# DR_EIB-128_Circle.net
KiCad netlist of a schematic drawn in EAGLE
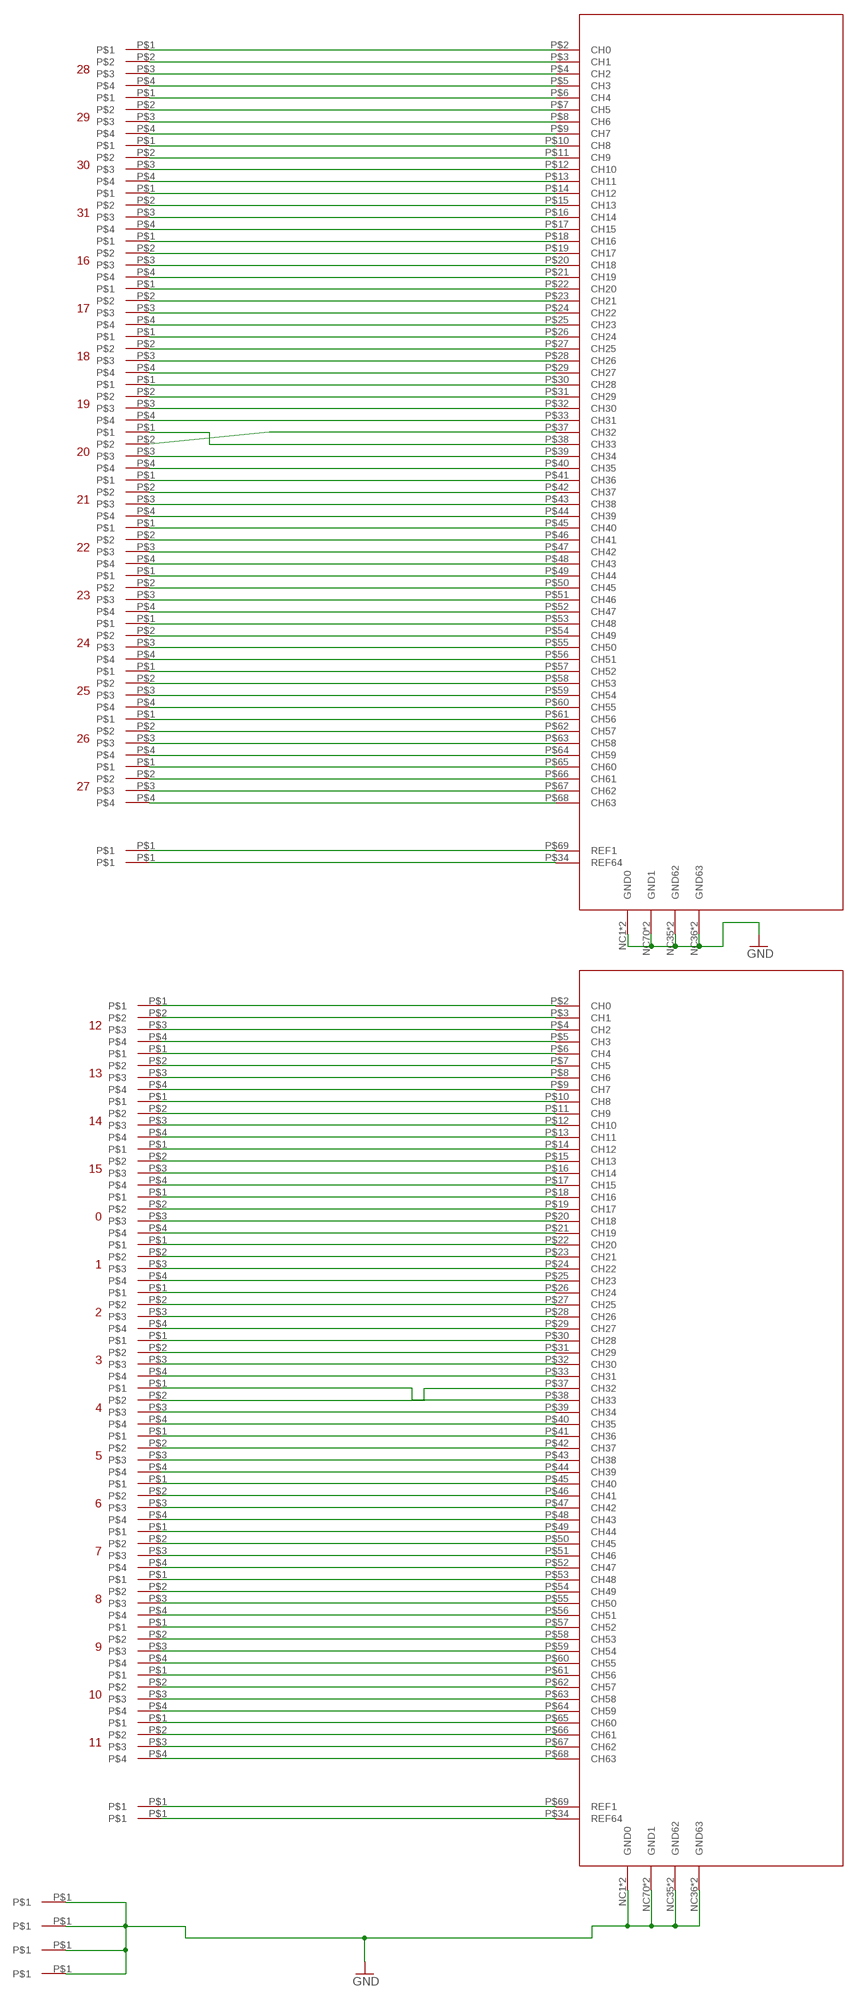
[diagram p0: schematic, sheet 1]

(export (version "E")
  (design (tool "Eeschema 10.0.6"))
  (components
    (comp (ref "0")
      (value "TETRODE_1.5IN_RADIUS")
      (footprint "eagle-import:TETRODE_1.5IN_RADIUS")
      (libsource (lib "eagle-import") (part "TETRODE_1.5IN_RADIUS"))
    )
    (comp (ref "1")
      (value "TETRODE_1.5IN_RADIUS")
      (footprint "eagle-import:TETRODE_1.5IN_RADIUS")
      (libsource (lib "eagle-import") (part "TETRODE_1.5IN_RADIUS"))
    )
    (comp (ref "2")
      (value "TETRODE_1.5IN_RADIUS")
      (footprint "eagle-import:TETRODE_1.5IN_RADIUS")
      (libsource (lib "eagle-import") (part "TETRODE_1.5IN_RADIUS"))
    )
    (comp (ref "3")
      (value "TETRODE_1.5IN_RADIUS")
      (footprint "eagle-import:TETRODE_1.5IN_RADIUS")
      (libsource (lib "eagle-import") (part "TETRODE_1.5IN_RADIUS"))
    )
    (comp (ref "4")
      (value "TETRODE_1.5IN_RADIUS")
      (footprint "eagle-import:TETRODE_1.5IN_RADIUS")
      (libsource (lib "eagle-import") (part "TETRODE_1.5IN_RADIUS"))
    )
    (comp (ref "5")
      (value "TETRODE_1.5IN_RADIUS")
      (footprint "eagle-import:TETRODE_1.5IN_RADIUS")
      (libsource (lib "eagle-import") (part "TETRODE_1.5IN_RADIUS"))
    )
    (comp (ref "6")
      (value "TETRODE_1.5IN_RADIUS")
      (footprint "eagle-import:TETRODE_1.5IN_RADIUS")
      (libsource (lib "eagle-import") (part "TETRODE_1.5IN_RADIUS"))
    )
    (comp (ref "7")
      (value "TETRODE_1.5IN_RADIUS")
      (footprint "eagle-import:TETRODE_1.5IN_RADIUS")
      (libsource (lib "eagle-import") (part "TETRODE_1.5IN_RADIUS"))
    )
    (comp (ref "8")
      (value "TETRODE_1.5IN_RADIUS")
      (footprint "eagle-import:TETRODE_1.5IN_RADIUS")
      (libsource (lib "eagle-import") (part "TETRODE_1.5IN_RADIUS"))
    )
    (comp (ref "9")
      (value "TETRODE_1.5IN_RADIUS")
      (footprint "eagle-import:TETRODE_1.5IN_RADIUS")
      (libsource (lib "eagle-import") (part "TETRODE_1.5IN_RADIUS"))
    )
    (comp (ref "10")
      (value "TETRODE_1.5IN_RADIUS")
      (footprint "eagle-import:TETRODE_1.5IN_RADIUS")
      (libsource (lib "eagle-import") (part "TETRODE_1.5IN_RADIUS"))
    )
    (comp (ref "11")
      (value "TETRODE_1.5IN_RADIUS")
      (footprint "eagle-import:TETRODE_1.5IN_RADIUS")
      (libsource (lib "eagle-import") (part "TETRODE_1.5IN_RADIUS"))
    )
    (comp (ref "12")
      (value "TETRODE_1.5IN_RADIUS")
      (footprint "eagle-import:TETRODE_1.5IN_RADIUS")
      (libsource (lib "eagle-import") (part "TETRODE_1.5IN_RADIUS"))
    )
    (comp (ref "13")
      (value "TETRODE_1.5IN_RADIUS")
      (footprint "eagle-import:TETRODE_1.5IN_RADIUS")
      (libsource (lib "eagle-import") (part "TETRODE_1.5IN_RADIUS"))
    )
    (comp (ref "14")
      (value "TETRODE_1.5IN_RADIUS")
      (footprint "eagle-import:TETRODE_1.5IN_RADIUS")
      (libsource (lib "eagle-import") (part "TETRODE_1.5IN_RADIUS"))
    )
    (comp (ref "15")
      (value "TETRODE_1.5IN_RADIUS")
      (footprint "eagle-import:TETRODE_1.5IN_RADIUS")
      (libsource (lib "eagle-import") (part "TETRODE_1.5IN_RADIUS"))
    )
    (comp (ref "16")
      (value "TETRODE_1.5IN_RADIUS")
      (footprint "eagle-import:TETRODE_1.5IN_RADIUS")
      (libsource (lib "eagle-import") (part "TETRODE_1.5IN_RADIUS"))
    )
    (comp (ref "17")
      (value "TETRODE_1.5IN_RADIUS")
      (footprint "eagle-import:TETRODE_1.5IN_RADIUS")
      (libsource (lib "eagle-import") (part "TETRODE_1.5IN_RADIUS"))
    )
    (comp (ref "18")
      (value "TETRODE_1.5IN_RADIUS")
      (footprint "eagle-import:TETRODE_1.5IN_RADIUS")
      (libsource (lib "eagle-import") (part "TETRODE_1.5IN_RADIUS"))
    )
    (comp (ref "19")
      (value "TETRODE_1.5IN_RADIUS")
      (footprint "eagle-import:TETRODE_1.5IN_RADIUS")
      (libsource (lib "eagle-import") (part "TETRODE_1.5IN_RADIUS"))
    )
    (comp (ref "20")
      (value "TETRODE_1.5IN_RADIUS")
      (footprint "eagle-import:TETRODE_1.5IN_RADIUS")
      (libsource (lib "eagle-import") (part "TETRODE_1.5IN_RADIUS"))
    )
    (comp (ref "21")
      (value "TETRODE_1.5IN_RADIUS")
      (footprint "eagle-import:TETRODE_1.5IN_RADIUS")
      (libsource (lib "eagle-import") (part "TETRODE_1.5IN_RADIUS"))
    )
    (comp (ref "22")
      (value "TETRODE_1.5IN_RADIUS")
      (footprint "eagle-import:TETRODE_1.5IN_RADIUS")
      (libsource (lib "eagle-import") (part "TETRODE_1.5IN_RADIUS"))
    )
    (comp (ref "23")
      (value "TETRODE_1.5IN_RADIUS")
      (footprint "eagle-import:TETRODE_1.5IN_RADIUS")
      (libsource (lib "eagle-import") (part "TETRODE_1.5IN_RADIUS"))
    )
    (comp (ref "24")
      (value "TETRODE_1.5IN_RADIUS")
      (footprint "eagle-import:TETRODE_1.5IN_RADIUS")
      (libsource (lib "eagle-import") (part "TETRODE_1.5IN_RADIUS"))
    )
    (comp (ref "25")
      (value "TETRODE_1.5IN_RADIUS")
      (footprint "eagle-import:TETRODE_1.5IN_RADIUS")
      (libsource (lib "eagle-import") (part "TETRODE_1.5IN_RADIUS"))
    )
    (comp (ref "26")
      (value "TETRODE_1.5IN_RADIUS")
      (footprint "eagle-import:TETRODE_1.5IN_RADIUS")
      (libsource (lib "eagle-import") (part "TETRODE_1.5IN_RADIUS"))
    )
    (comp (ref "27")
      (value "TETRODE_1.5IN_RADIUS")
      (footprint "eagle-import:TETRODE_1.5IN_RADIUS")
      (libsource (lib "eagle-import") (part "TETRODE_1.5IN_RADIUS"))
    )
    (comp (ref "28")
      (value "TETRODE_1.5IN_RADIUS")
      (footprint "eagle-import:TETRODE_1.5IN_RADIUS")
      (libsource (lib "eagle-import") (part "TETRODE_1.5IN_RADIUS"))
    )
    (comp (ref "29")
      (value "TETRODE_1.5IN_RADIUS")
      (footprint "eagle-import:TETRODE_1.5IN_RADIUS")
      (libsource (lib "eagle-import") (part "TETRODE_1.5IN_RADIUS"))
    )
    (comp (ref "30")
      (value "TETRODE_1.5IN_RADIUS")
      (footprint "eagle-import:TETRODE_1.5IN_RADIUS")
      (libsource (lib "eagle-import") (part "TETRODE_1.5IN_RADIUS"))
    )
    (comp (ref "31")
      (value "TETRODE_1.5IN_RADIUS")
      (footprint "eagle-import:TETRODE_1.5IN_RADIUS")
      (libsource (lib "eagle-import") (part "TETRODE_1.5IN_RADIUS"))
    )
    (comp (ref "U$1")
      (value "TARRAYSHUTTLEHOLE")
      (footprint "eagle-import:TARRAYSHUTTLEHOLE")
      (libsource (lib "eagle-import") (part "TARRAYSHUTTLEHOLE"))
    )
    (comp (ref "U$2")
      (value "TARRAYSHUTTLEHOLE")
      (footprint "eagle-import:TARRAYSHUTTLEHOLE")
      (libsource (lib "eagle-import") (part "TARRAYSHUTTLEHOLE"))
    )
    (comp (ref "U$4")
      (value "TARRAYSHUTTLEHOLE")
      (footprint "eagle-import:TARRAYSHUTTLEHOLE")
      (libsource (lib "eagle-import") (part "TARRAYSHUTTLEHOLE"))
    )
    (comp (ref "U$5")
      (value "TARRAYSHUTTLEHOLE")
      (footprint "eagle-import:TARRAYSHUTTLEHOLE")
      (libsource (lib "eagle-import") (part "TARRAYSHUTTLEHOLE"))
    )
    (comp (ref "U$6")
      (value "TARRAYSHUTTLEHOLE")
      (footprint "eagle-import:TARRAYSHUTTLEHOLE")
      (libsource (lib "eagle-import") (part "TARRAYSHUTTLEHOLE"))
    )
    (comp (ref "U$7")
      (value "TARRAYSHUTTLEHOLE")
      (footprint "eagle-import:TARRAYSHUTTLEHOLE")
      (libsource (lib "eagle-import") (part "TARRAYSHUTTLEHOLE"))
    )
    (comp (ref "U$8")
      (value "TARRAYSHUTTLEHOLE")
      (footprint "eagle-import:TARRAYSHUTTLEHOLE")
      (libsource (lib "eagle-import") (part "TARRAYSHUTTLEHOLE"))
    )
    (comp (ref "U$9")
      (value "TARRAYSHUTTLEHOLE")
      (footprint "eagle-import:TARRAYSHUTTLEHOLE")
      (libsource (lib "eagle-import") (part "TARRAYSHUTTLEHOLE"))
    )
    (comp (ref "U$10")
      (value "HIROSE-70PIN-HEADER-SEQUENTIAL")
      (footprint "eagle-import:DF40C-70DP-0.4V")
      (libsource (lib "eagle-import") (part "HIROSE-70PIN-HEADER-SEQUENTIAL"))
    )
    (comp (ref "U$11")
      (value "HIROSE-70PIN-HEADER-SEQUENTIAL")
      (footprint "eagle-import:DF40C-70DP-0.4V")
      (libsource (lib "eagle-import") (part "HIROSE-70PIN-HEADER-SEQUENTIAL"))
    )
  )
  (nets
    (net (code "1") (name "GND") (class "Default")
      (node (ref "U$1") (pin "P$1") (pinfunction "P$1_P$1") (pintype "bidirectional"))
      (node (ref "U$10") (pin "NC1") (pinfunction "GND0_NC1") (pintype "power_in"))
      (node (ref "U$10") (pin "NC35") (pinfunction "GND62_NC35") (pintype "power_in"))
      (node (ref "U$10") (pin "NC36") (pinfunction "GND63_NC36") (pintype "power_in"))
      (node (ref "U$10") (pin "NC70") (pinfunction "GND1_NC70") (pintype "power_in"))
      (node (ref "U$10") (pin "P$1") (pinfunction "GND0_P$1") (pintype "power_in"))
      (node (ref "U$10") (pin "P$35") (pinfunction "GND62_P$35") (pintype "power_in"))
      (node (ref "U$10") (pin "P$36") (pinfunction "GND63_P$36") (pintype "power_in"))
      (node (ref "U$10") (pin "P$70") (pinfunction "GND1_P$70") (pintype "power_in"))
      (node (ref "U$11") (pin "NC1") (pinfunction "GND0_NC1") (pintype "power_in"))
      (node (ref "U$11") (pin "NC35") (pinfunction "GND62_NC35") (pintype "power_in"))
      (node (ref "U$11") (pin "NC36") (pinfunction "GND63_NC36") (pintype "power_in"))
      (node (ref "U$11") (pin "NC70") (pinfunction "GND1_NC70") (pintype "power_in"))
      (node (ref "U$11") (pin "P$1") (pinfunction "GND0_P$1") (pintype "power_in"))
      (node (ref "U$11") (pin "P$35") (pinfunction "GND62_P$35") (pintype "power_in"))
      (node (ref "U$11") (pin "P$36") (pinfunction "GND63_P$36") (pintype "power_in"))
      (node (ref "U$11") (pin "P$70") (pinfunction "GND1_P$70") (pintype "power_in"))
      (node (ref "U$2") (pin "P$1") (pinfunction "P$1_P$1") (pintype "bidirectional"))
      (node (ref "U$4") (pin "P$1") (pinfunction "P$1_P$1") (pintype "bidirectional"))
      (node (ref "U$5") (pin "P$1") (pinfunction "P$1_P$1") (pintype "bidirectional"))
    )
    (net (code "2") (name "Net-(U$10-CH0)") (class "Default")
      (node (ref "28") (pin "P$1") (pinfunction "P$1_P$1") (pintype "bidirectional"))
      (node (ref "U$10") (pin "P$2") (pinfunction "CH0_P$2") (pintype "input"))
    )
    (net (code "3") (name "Net-(U$10-CH1)") (class "Default")
      (node (ref "28") (pin "P$2") (pinfunction "P$2_P$2") (pintype "bidirectional"))
      (node (ref "U$10") (pin "P$3") (pinfunction "CH1_P$3") (pintype "input"))
    )
    (net (code "4") (name "Net-(U$10-CH2)") (class "Default")
      (node (ref "28") (pin "P$3") (pinfunction "P$3_P$3") (pintype "bidirectional"))
      (node (ref "U$10") (pin "P$4") (pinfunction "CH2_P$4") (pintype "input"))
    )
    (net (code "5") (name "Net-(U$10-CH3)") (class "Default")
      (node (ref "28") (pin "P$4") (pinfunction "P$4_P$4") (pintype "bidirectional"))
      (node (ref "U$10") (pin "P$5") (pinfunction "CH3_P$5") (pintype "input"))
    )
    (net (code "6") (name "Net-(U$10-CH4)") (class "Default")
      (node (ref "29") (pin "P$1") (pinfunction "P$1_P$1") (pintype "bidirectional"))
      (node (ref "U$10") (pin "P$6") (pinfunction "CH4_P$6") (pintype "input"))
    )
    (net (code "7") (name "Net-(U$10-CH5)") (class "Default")
      (node (ref "29") (pin "P$2") (pinfunction "P$2_P$2") (pintype "bidirectional"))
      (node (ref "U$10") (pin "P$7") (pinfunction "CH5_P$7") (pintype "input"))
    )
    (net (code "8") (name "Net-(U$10-CH6)") (class "Default")
      (node (ref "29") (pin "P$3") (pinfunction "P$3_P$3") (pintype "bidirectional"))
      (node (ref "U$10") (pin "P$8") (pinfunction "CH6_P$8") (pintype "input"))
    )
    (net (code "9") (name "Net-(U$10-CH7)") (class "Default")
      (node (ref "29") (pin "P$4") (pinfunction "P$4_P$4") (pintype "bidirectional"))
      (node (ref "U$10") (pin "P$9") (pinfunction "CH7_P$9") (pintype "input"))
    )
    (net (code "10") (name "Net-(U$10-CH8)") (class "Default")
      (node (ref "30") (pin "P$1") (pinfunction "P$1_P$1") (pintype "bidirectional"))
      (node (ref "U$10") (pin "P$10") (pinfunction "CH8_P$10") (pintype "input"))
    )
    (net (code "11") (name "Net-(U$10-CH9)") (class "Default")
      (node (ref "30") (pin "P$2") (pinfunction "P$2_P$2") (pintype "bidirectional"))
      (node (ref "U$10") (pin "P$11") (pinfunction "CH9_P$11") (pintype "input"))
    )
    (net (code "12") (name "Net-(U$10-CH10)") (class "Default")
      (node (ref "30") (pin "P$3") (pinfunction "P$3_P$3") (pintype "bidirectional"))
      (node (ref "U$10") (pin "P$12") (pinfunction "CH10_P$12") (pintype "input"))
    )
    (net (code "13") (name "Net-(U$10-CH11)") (class "Default")
      (node (ref "30") (pin "P$4") (pinfunction "P$4_P$4") (pintype "bidirectional"))
      (node (ref "U$10") (pin "P$13") (pinfunction "CH11_P$13") (pintype "input"))
    )
    (net (code "14") (name "Net-(U$10-CH12)") (class "Default")
      (node (ref "31") (pin "P$1") (pinfunction "P$1_P$1") (pintype "bidirectional"))
      (node (ref "U$10") (pin "P$14") (pinfunction "CH12_P$14") (pintype "input"))
    )
    (net (code "15") (name "Net-(U$10-CH13)") (class "Default")
      (node (ref "31") (pin "P$2") (pinfunction "P$2_P$2") (pintype "bidirectional"))
      (node (ref "U$10") (pin "P$15") (pinfunction "CH13_P$15") (pintype "input"))
    )
    (net (code "16") (name "Net-(U$10-CH14)") (class "Default")
      (node (ref "31") (pin "P$3") (pinfunction "P$3_P$3") (pintype "bidirectional"))
      (node (ref "U$10") (pin "P$16") (pinfunction "CH14_P$16") (pintype "input"))
    )
    (net (code "17") (name "Net-(U$10-CH15)") (class "Default")
      (node (ref "31") (pin "P$4") (pinfunction "P$4_P$4") (pintype "bidirectional"))
      (node (ref "U$10") (pin "P$17") (pinfunction "CH15_P$17") (pintype "input"))
    )
    (net (code "18") (name "Net-(U$10-CH16)") (class "Default")
      (node (ref "16") (pin "P$1") (pinfunction "P$1_P$1") (pintype "bidirectional"))
      (node (ref "U$10") (pin "P$18") (pinfunction "CH16_P$18") (pintype "input"))
    )
    (net (code "19") (name "Net-(U$10-CH17)") (class "Default")
      (node (ref "16") (pin "P$2") (pinfunction "P$2_P$2") (pintype "bidirectional"))
      (node (ref "U$10") (pin "P$19") (pinfunction "CH17_P$19") (pintype "input"))
    )
    (net (code "20") (name "Net-(U$10-CH18)") (class "Default")
      (node (ref "16") (pin "P$3") (pinfunction "P$3_P$3") (pintype "bidirectional"))
      (node (ref "U$10") (pin "P$20") (pinfunction "CH18_P$20") (pintype "input"))
    )
    (net (code "21") (name "Net-(U$10-CH19)") (class "Default")
      (node (ref "16") (pin "P$4") (pinfunction "P$4_P$4") (pintype "bidirectional"))
      (node (ref "U$10") (pin "P$21") (pinfunction "CH19_P$21") (pintype "input"))
    )
    (net (code "22") (name "Net-(U$10-CH20)") (class "Default")
      (node (ref "17") (pin "P$1") (pinfunction "P$1_P$1") (pintype "bidirectional"))
      (node (ref "U$10") (pin "P$22") (pinfunction "CH20_P$22") (pintype "input"))
    )
    (net (code "23") (name "Net-(U$10-CH21)") (class "Default")
      (node (ref "17") (pin "P$2") (pinfunction "P$2_P$2") (pintype "bidirectional"))
      (node (ref "U$10") (pin "P$23") (pinfunction "CH21_P$23") (pintype "input"))
    )
    (net (code "24") (name "Net-(U$10-CH22)") (class "Default")
      (node (ref "17") (pin "P$3") (pinfunction "P$3_P$3") (pintype "bidirectional"))
      (node (ref "U$10") (pin "P$24") (pinfunction "CH22_P$24") (pintype "input"))
    )
    (net (code "25") (name "Net-(U$10-CH23)") (class "Default")
      (node (ref "17") (pin "P$4") (pinfunction "P$4_P$4") (pintype "bidirectional"))
      (node (ref "U$10") (pin "P$25") (pinfunction "CH23_P$25") (pintype "input"))
    )
    (net (code "26") (name "Net-(U$10-CH24)") (class "Default")
      (node (ref "18") (pin "P$1") (pinfunction "P$1_P$1") (pintype "bidirectional"))
      (node (ref "U$10") (pin "P$26") (pinfunction "CH24_P$26") (pintype "input"))
    )
    (net (code "27") (name "Net-(U$10-CH25)") (class "Default")
      (node (ref "18") (pin "P$2") (pinfunction "P$2_P$2") (pintype "bidirectional"))
      (node (ref "U$10") (pin "P$27") (pinfunction "CH25_P$27") (pintype "input"))
    )
    (net (code "28") (name "Net-(U$10-CH26)") (class "Default")
      (node (ref "18") (pin "P$3") (pinfunction "P$3_P$3") (pintype "bidirectional"))
      (node (ref "U$10") (pin "P$28") (pinfunction "CH26_P$28") (pintype "input"))
    )
    (net (code "29") (name "Net-(U$10-CH27)") (class "Default")
      (node (ref "18") (pin "P$4") (pinfunction "P$4_P$4") (pintype "bidirectional"))
      (node (ref "U$10") (pin "P$29") (pinfunction "CH27_P$29") (pintype "input"))
    )
    (net (code "30") (name "Net-(U$10-CH28)") (class "Default")
      (node (ref "19") (pin "P$1") (pinfunction "P$1_P$1") (pintype "bidirectional"))
      (node (ref "U$10") (pin "P$30") (pinfunction "CH28_P$30") (pintype "input"))
    )
    (net (code "31") (name "Net-(U$10-CH29)") (class "Default")
      (node (ref "19") (pin "P$2") (pinfunction "P$2_P$2") (pintype "bidirectional"))
      (node (ref "U$10") (pin "P$31") (pinfunction "CH29_P$31") (pintype "input"))
    )
    (net (code "32") (name "Net-(U$10-CH30)") (class "Default")
      (node (ref "19") (pin "P$3") (pinfunction "P$3_P$3") (pintype "bidirectional"))
      (node (ref "U$10") (pin "P$32") (pinfunction "CH30_P$32") (pintype "input"))
    )
    (net (code "33") (name "Net-(U$10-CH31)") (class "Default")
      (node (ref "19") (pin "P$4") (pinfunction "P$4_P$4") (pintype "bidirectional"))
      (node (ref "U$10") (pin "P$33") (pinfunction "CH31_P$33") (pintype "input"))
    )
    (net (code "34") (name "Net-(U$10-CH32)") (class "Default")
      (node (ref "20") (pin "P$2") (pinfunction "P$2_P$2") (pintype "bidirectional"))
      (node (ref "U$10") (pin "P$37") (pinfunction "CH32_P$37") (pintype "input"))
    )
    (net (code "35") (name "Net-(U$10-CH33)") (class "Default")
      (node (ref "20") (pin "P$1") (pinfunction "P$1_P$1") (pintype "bidirectional"))
      (node (ref "U$10") (pin "P$38") (pinfunction "CH33_P$38") (pintype "input"))
    )
    (net (code "36") (name "Net-(U$10-CH34)") (class "Default")
      (node (ref "20") (pin "P$3") (pinfunction "P$3_P$3") (pintype "bidirectional"))
      (node (ref "U$10") (pin "P$39") (pinfunction "CH34_P$39") (pintype "input"))
    )
    (net (code "37") (name "Net-(U$10-CH35)") (class "Default")
      (node (ref "20") (pin "P$4") (pinfunction "P$4_P$4") (pintype "bidirectional"))
      (node (ref "U$10") (pin "P$40") (pinfunction "CH35_P$40") (pintype "input"))
    )
    (net (code "38") (name "Net-(U$10-CH36)") (class "Default")
      (node (ref "21") (pin "P$1") (pinfunction "P$1_P$1") (pintype "bidirectional"))
      (node (ref "U$10") (pin "P$41") (pinfunction "CH36_P$41") (pintype "input"))
    )
    (net (code "39") (name "Net-(U$10-CH37)") (class "Default")
      (node (ref "21") (pin "P$2") (pinfunction "P$2_P$2") (pintype "bidirectional"))
      (node (ref "U$10") (pin "P$42") (pinfunction "CH37_P$42") (pintype "input"))
    )
    (net (code "40") (name "Net-(U$10-CH38)") (class "Default")
      (node (ref "21") (pin "P$3") (pinfunction "P$3_P$3") (pintype "bidirectional"))
      (node (ref "U$10") (pin "P$43") (pinfunction "CH38_P$43") (pintype "input"))
    )
    (net (code "41") (name "Net-(U$10-CH39)") (class "Default")
      (node (ref "21") (pin "P$4") (pinfunction "P$4_P$4") (pintype "bidirectional"))
      (node (ref "U$10") (pin "P$44") (pinfunction "CH39_P$44") (pintype "input"))
    )
    (net (code "42") (name "Net-(U$10-CH40)") (class "Default")
      (node (ref "22") (pin "P$1") (pinfunction "P$1_P$1") (pintype "bidirectional"))
      (node (ref "U$10") (pin "P$45") (pinfunction "CH40_P$45") (pintype "input"))
    )
    (net (code "43") (name "Net-(U$10-CH41)") (class "Default")
      (node (ref "22") (pin "P$2") (pinfunction "P$2_P$2") (pintype "bidirectional"))
      (node (ref "U$10") (pin "P$46") (pinfunction "CH41_P$46") (pintype "input"))
    )
    (net (code "44") (name "Net-(U$10-CH42)") (class "Default")
      (node (ref "22") (pin "P$3") (pinfunction "P$3_P$3") (pintype "bidirectional"))
      (node (ref "U$10") (pin "P$47") (pinfunction "CH42_P$47") (pintype "input"))
    )
    (net (code "45") (name "Net-(U$10-CH43)") (class "Default")
      (node (ref "22") (pin "P$4") (pinfunction "P$4_P$4") (pintype "bidirectional"))
      (node (ref "U$10") (pin "P$48") (pinfunction "CH43_P$48") (pintype "input"))
    )
    (net (code "46") (name "Net-(U$10-CH44)") (class "Default")
      (node (ref "23") (pin "P$1") (pinfunction "P$1_P$1") (pintype "bidirectional"))
      (node (ref "U$10") (pin "P$49") (pinfunction "CH44_P$49") (pintype "input"))
    )
    (net (code "47") (name "Net-(U$10-CH45)") (class "Default")
      (node (ref "23") (pin "P$2") (pinfunction "P$2_P$2") (pintype "bidirectional"))
      (node (ref "U$10") (pin "P$50") (pinfunction "CH45_P$50") (pintype "input"))
    )
    (net (code "48") (name "Net-(U$10-CH46)") (class "Default")
      (node (ref "23") (pin "P$3") (pinfunction "P$3_P$3") (pintype "bidirectional"))
      (node (ref "U$10") (pin "P$51") (pinfunction "CH46_P$51") (pintype "input"))
    )
    (net (code "49") (name "Net-(U$10-CH47)") (class "Default")
      (node (ref "23") (pin "P$4") (pinfunction "P$4_P$4") (pintype "bidirectional"))
      (node (ref "U$10") (pin "P$52") (pinfunction "CH47_P$52") (pintype "input"))
    )
    (net (code "50") (name "Net-(U$10-CH48)") (class "Default")
      (node (ref "24") (pin "P$1") (pinfunction "P$1_P$1") (pintype "bidirectional"))
      (node (ref "U$10") (pin "P$53") (pinfunction "CH48_P$53") (pintype "input"))
    )
    (net (code "51") (name "Net-(U$10-CH49)") (class "Default")
      (node (ref "24") (pin "P$2") (pinfunction "P$2_P$2") (pintype "bidirectional"))
      (node (ref "U$10") (pin "P$54") (pinfunction "CH49_P$54") (pintype "input"))
    )
    (net (code "52") (name "Net-(U$10-CH50)") (class "Default")
      (node (ref "24") (pin "P$3") (pinfunction "P$3_P$3") (pintype "bidirectional"))
      (node (ref "U$10") (pin "P$55") (pinfunction "CH50_P$55") (pintype "input"))
    )
    (net (code "53") (name "Net-(U$10-CH51)") (class "Default")
      (node (ref "24") (pin "P$4") (pinfunction "P$4_P$4") (pintype "bidirectional"))
      (node (ref "U$10") (pin "P$56") (pinfunction "CH51_P$56") (pintype "input"))
    )
    (net (code "54") (name "Net-(U$10-CH52)") (class "Default")
      (node (ref "25") (pin "P$1") (pinfunction "P$1_P$1") (pintype "bidirectional"))
      (node (ref "U$10") (pin "P$57") (pinfunction "CH52_P$57") (pintype "input"))
    )
    (net (code "55") (name "Net-(U$10-CH53)") (class "Default")
      (node (ref "25") (pin "P$2") (pinfunction "P$2_P$2") (pintype "bidirectional"))
      (node (ref "U$10") (pin "P$58") (pinfunction "CH53_P$58") (pintype "input"))
    )
    (net (code "56") (name "Net-(U$10-CH54)") (class "Default")
      (node (ref "25") (pin "P$3") (pinfunction "P$3_P$3") (pintype "bidirectional"))
      (node (ref "U$10") (pin "P$59") (pinfunction "CH54_P$59") (pintype "input"))
    )
    (net (code "57") (name "Net-(U$10-CH55)") (class "Default")
      (node (ref "25") (pin "P$4") (pinfunction "P$4_P$4") (pintype "bidirectional"))
      (node (ref "U$10") (pin "P$60") (pinfunction "CH55_P$60") (pintype "input"))
    )
    (net (code "58") (name "Net-(U$10-CH56)") (class "Default")
      (node (ref "26") (pin "P$1") (pinfunction "P$1_P$1") (pintype "bidirectional"))
      (node (ref "U$10") (pin "P$61") (pinfunction "CH56_P$61") (pintype "input"))
    )
    (net (code "59") (name "Net-(U$10-CH57)") (class "Default")
      (node (ref "26") (pin "P$2") (pinfunction "P$2_P$2") (pintype "bidirectional"))
      (node (ref "U$10") (pin "P$62") (pinfunction "CH57_P$62") (pintype "input"))
    )
    (net (code "60") (name "Net-(U$10-CH58)") (class "Default")
      (node (ref "26") (pin "P$3") (pinfunction "P$3_P$3") (pintype "bidirectional"))
      (node (ref "U$10") (pin "P$63") (pinfunction "CH58_P$63") (pintype "input"))
    )
    (net (code "61") (name "Net-(U$10-CH59)") (class "Default")
      (node (ref "26") (pin "P$4") (pinfunction "P$4_P$4") (pintype "bidirectional"))
      (node (ref "U$10") (pin "P$64") (pinfunction "CH59_P$64") (pintype "input"))
    )
    (net (code "62") (name "Net-(U$10-CH60)") (class "Default")
      (node (ref "27") (pin "P$1") (pinfunction "P$1_P$1") (pintype "bidirectional"))
      (node (ref "U$10") (pin "P$65") (pinfunction "CH60_P$65") (pintype "input"))
    )
    (net (code "63") (name "Net-(U$10-CH61)") (class "Default")
      (node (ref "27") (pin "P$2") (pinfunction "P$2_P$2") (pintype "bidirectional"))
      (node (ref "U$10") (pin "P$66") (pinfunction "CH61_P$66") (pintype "input"))
    )
    (net (code "64") (name "Net-(U$10-CH62)") (class "Default")
      (node (ref "27") (pin "P$3") (pinfunction "P$3_P$3") (pintype "bidirectional"))
      (node (ref "U$10") (pin "P$67") (pinfunction "CH62_P$67") (pintype "input"))
    )
    (net (code "65") (name "Net-(U$10-CH63)") (class "Default")
      (node (ref "27") (pin "P$4") (pinfunction "P$4_P$4") (pintype "bidirectional"))
      (node (ref "U$10") (pin "P$68") (pinfunction "CH63_P$68") (pintype "input"))
    )
    (net (code "66") (name "Net-(U$10-REF1)") (class "Default")
      (node (ref "U$10") (pin "P$69") (pinfunction "REF1_P$69") (pintype "input"))
      (node (ref "U$7") (pin "P$1") (pinfunction "P$1_P$1") (pintype "bidirectional"))
    )
    (net (code "67") (name "Net-(U$10-REF64)") (class "Default")
      (node (ref "U$10") (pin "P$34") (pinfunction "REF64_P$34") (pintype "input"))
      (node (ref "U$6") (pin "P$1") (pinfunction "P$1_P$1") (pintype "bidirectional"))
    )
    (net (code "68") (name "Net-(U$11-CH0)") (class "Default")
      (node (ref "12") (pin "P$1") (pinfunction "P$1_P$1") (pintype "bidirectional"))
      (node (ref "U$11") (pin "P$2") (pinfunction "CH0_P$2") (pintype "input"))
    )
    (net (code "69") (name "Net-(U$11-CH1)") (class "Default")
      (node (ref "12") (pin "P$2") (pinfunction "P$2_P$2") (pintype "bidirectional"))
      (node (ref "U$11") (pin "P$3") (pinfunction "CH1_P$3") (pintype "input"))
    )
    (net (code "70") (name "Net-(U$11-CH2)") (class "Default")
      (node (ref "12") (pin "P$3") (pinfunction "P$3_P$3") (pintype "bidirectional"))
      (node (ref "U$11") (pin "P$4") (pinfunction "CH2_P$4") (pintype "input"))
    )
    (net (code "71") (name "Net-(U$11-CH3)") (class "Default")
      (node (ref "12") (pin "P$4") (pinfunction "P$4_P$4") (pintype "bidirectional"))
      (node (ref "U$11") (pin "P$5") (pinfunction "CH3_P$5") (pintype "input"))
    )
    (net (code "72") (name "Net-(U$11-CH4)") (class "Default")
      (node (ref "13") (pin "P$1") (pinfunction "P$1_P$1") (pintype "bidirectional"))
      (node (ref "U$11") (pin "P$6") (pinfunction "CH4_P$6") (pintype "input"))
    )
    (net (code "73") (name "Net-(U$11-CH5)") (class "Default")
      (node (ref "13") (pin "P$2") (pinfunction "P$2_P$2") (pintype "bidirectional"))
      (node (ref "U$11") (pin "P$7") (pinfunction "CH5_P$7") (pintype "input"))
    )
    (net (code "74") (name "Net-(U$11-CH6)") (class "Default")
      (node (ref "13") (pin "P$3") (pinfunction "P$3_P$3") (pintype "bidirectional"))
      (node (ref "U$11") (pin "P$8") (pinfunction "CH6_P$8") (pintype "input"))
    )
    (net (code "75") (name "Net-(U$11-CH7)") (class "Default")
      (node (ref "13") (pin "P$4") (pinfunction "P$4_P$4") (pintype "bidirectional"))
      (node (ref "U$11") (pin "P$9") (pinfunction "CH7_P$9") (pintype "input"))
    )
    (net (code "76") (name "Net-(U$11-CH8)") (class "Default")
      (node (ref "14") (pin "P$1") (pinfunction "P$1_P$1") (pintype "bidirectional"))
      (node (ref "U$11") (pin "P$10") (pinfunction "CH8_P$10") (pintype "input"))
    )
    (net (code "77") (name "Net-(U$11-CH9)") (class "Default")
      (node (ref "14") (pin "P$2") (pinfunction "P$2_P$2") (pintype "bidirectional"))
      (node (ref "U$11") (pin "P$11") (pinfunction "CH9_P$11") (pintype "input"))
    )
    (net (code "78") (name "Net-(U$11-CH10)") (class "Default")
      (node (ref "14") (pin "P$3") (pinfunction "P$3_P$3") (pintype "bidirectional"))
      (node (ref "U$11") (pin "P$12") (pinfunction "CH10_P$12") (pintype "input"))
    )
    (net (code "79") (name "Net-(U$11-CH11)") (class "Default")
      (node (ref "14") (pin "P$4") (pinfunction "P$4_P$4") (pintype "bidirectional"))
      (node (ref "U$11") (pin "P$13") (pinfunction "CH11_P$13") (pintype "input"))
    )
    (net (code "80") (name "Net-(U$11-CH12)") (class "Default")
      (node (ref "15") (pin "P$1") (pinfunction "P$1_P$1") (pintype "bidirectional"))
      (node (ref "U$11") (pin "P$14") (pinfunction "CH12_P$14") (pintype "input"))
    )
    (net (code "81") (name "Net-(U$11-CH13)") (class "Default")
      (node (ref "15") (pin "P$2") (pinfunction "P$2_P$2") (pintype "bidirectional"))
      (node (ref "U$11") (pin "P$15") (pinfunction "CH13_P$15") (pintype "input"))
    )
    (net (code "82") (name "Net-(U$11-CH14)") (class "Default")
      (node (ref "15") (pin "P$3") (pinfunction "P$3_P$3") (pintype "bidirectional"))
      (node (ref "U$11") (pin "P$16") (pinfunction "CH14_P$16") (pintype "input"))
    )
    (net (code "83") (name "Net-(U$11-CH15)") (class "Default")
      (node (ref "15") (pin "P$4") (pinfunction "P$4_P$4") (pintype "bidirectional"))
      (node (ref "U$11") (pin "P$17") (pinfunction "CH15_P$17") (pintype "input"))
    )
    (net (code "84") (name "Net-(U$11-CH16)") (class "Default")
      (node (ref "0") (pin "P$1") (pinfunction "P$1_P$1") (pintype "bidirectional"))
      (node (ref "U$11") (pin "P$18") (pinfunction "CH16_P$18") (pintype "input"))
    )
    (net (code "85") (name "Net-(U$11-CH17)") (class "Default")
      (node (ref "0") (pin "P$2") (pinfunction "P$2_P$2") (pintype "bidirectional"))
      (node (ref "U$11") (pin "P$19") (pinfunction "CH17_P$19") (pintype "input"))
    )
    (net (code "86") (name "Net-(U$11-CH18)") (class "Default")
      (node (ref "0") (pin "P$3") (pinfunction "P$3_P$3") (pintype "bidirectional"))
      (node (ref "U$11") (pin "P$20") (pinfunction "CH18_P$20") (pintype "input"))
    )
    (net (code "87") (name "Net-(U$11-CH19)") (class "Default")
      (node (ref "0") (pin "P$4") (pinfunction "P$4_P$4") (pintype "bidirectional"))
      (node (ref "U$11") (pin "P$21") (pinfunction "CH19_P$21") (pintype "input"))
    )
    (net (code "88") (name "Net-(U$11-CH20)") (class "Default")
      (node (ref "1") (pin "P$1") (pinfunction "P$1_P$1") (pintype "bidirectional"))
      (node (ref "U$11") (pin "P$22") (pinfunction "CH20_P$22") (pintype "input"))
    )
    (net (code "89") (name "Net-(U$11-CH21)") (class "Default")
      (node (ref "1") (pin "P$2") (pinfunction "P$2_P$2") (pintype "bidirectional"))
      (node (ref "U$11") (pin "P$23") (pinfunction "CH21_P$23") (pintype "input"))
    )
    (net (code "90") (name "Net-(U$11-CH22)") (class "Default")
      (node (ref "1") (pin "P$3") (pinfunction "P$3_P$3") (pintype "bidirectional"))
      (node (ref "U$11") (pin "P$24") (pinfunction "CH22_P$24") (pintype "input"))
    )
    (net (code "91") (name "Net-(U$11-CH23)") (class "Default")
      (node (ref "1") (pin "P$4") (pinfunction "P$4_P$4") (pintype "bidirectional"))
      (node (ref "U$11") (pin "P$25") (pinfunction "CH23_P$25") (pintype "input"))
    )
    (net (code "92") (name "Net-(U$11-CH24)") (class "Default")
      (node (ref "2") (pin "P$1") (pinfunction "P$1_P$1") (pintype "bidirectional"))
      (node (ref "U$11") (pin "P$26") (pinfunction "CH24_P$26") (pintype "input"))
    )
    (net (code "93") (name "Net-(U$11-CH25)") (class "Default")
      (node (ref "2") (pin "P$2") (pinfunction "P$2_P$2") (pintype "bidirectional"))
      (node (ref "U$11") (pin "P$27") (pinfunction "CH25_P$27") (pintype "input"))
    )
    (net (code "94") (name "Net-(U$11-CH26)") (class "Default")
      (node (ref "2") (pin "P$3") (pinfunction "P$3_P$3") (pintype "bidirectional"))
      (node (ref "U$11") (pin "P$28") (pinfunction "CH26_P$28") (pintype "input"))
    )
    (net (code "95") (name "Net-(U$11-CH27)") (class "Default")
      (node (ref "2") (pin "P$4") (pinfunction "P$4_P$4") (pintype "bidirectional"))
      (node (ref "U$11") (pin "P$29") (pinfunction "CH27_P$29") (pintype "input"))
    )
    (net (code "96") (name "Net-(U$11-CH28)") (class "Default")
      (node (ref "3") (pin "P$1") (pinfunction "P$1_P$1") (pintype "bidirectional"))
      (node (ref "U$11") (pin "P$30") (pinfunction "CH28_P$30") (pintype "input"))
    )
    (net (code "97") (name "Net-(U$11-CH29)") (class "Default")
      (node (ref "3") (pin "P$2") (pinfunction "P$2_P$2") (pintype "bidirectional"))
      (node (ref "U$11") (pin "P$31") (pinfunction "CH29_P$31") (pintype "input"))
    )
    (net (code "98") (name "Net-(U$11-CH30)") (class "Default")
      (node (ref "3") (pin "P$3") (pinfunction "P$3_P$3") (pintype "bidirectional"))
      (node (ref "U$11") (pin "P$32") (pinfunction "CH30_P$32") (pintype "input"))
    )
    (net (code "99") (name "Net-(U$11-CH31)") (class "Default")
      (node (ref "3") (pin "P$4") (pinfunction "P$4_P$4") (pintype "bidirectional"))
      (node (ref "U$11") (pin "P$33") (pinfunction "CH31_P$33") (pintype "input"))
    )
    (net (code "100") (name "Net-(U$11-CH32)") (class "Default")
      (node (ref "4") (pin "P$2") (pinfunction "P$2_P$2") (pintype "bidirectional"))
      (node (ref "U$11") (pin "P$37") (pinfunction "CH32_P$37") (pintype "input"))
    )
    (net (code "101") (name "Net-(U$11-CH33)") (class "Default")
      (node (ref "4") (pin "P$1") (pinfunction "P$1_P$1") (pintype "bidirectional"))
      (node (ref "U$11") (pin "P$38") (pinfunction "CH33_P$38") (pintype "input"))
    )
    (net (code "102") (name "Net-(U$11-CH34)") (class "Default")
      (node (ref "4") (pin "P$3") (pinfunction "P$3_P$3") (pintype "bidirectional"))
      (node (ref "U$11") (pin "P$39") (pinfunction "CH34_P$39") (pintype "input"))
    )
    (net (code "103") (name "Net-(U$11-CH35)") (class "Default")
      (node (ref "4") (pin "P$4") (pinfunction "P$4_P$4") (pintype "bidirectional"))
      (node (ref "U$11") (pin "P$40") (pinfunction "CH35_P$40") (pintype "input"))
    )
    (net (code "104") (name "Net-(U$11-CH36)") (class "Default")
      (node (ref "5") (pin "P$1") (pinfunction "P$1_P$1") (pintype "bidirectional"))
      (node (ref "U$11") (pin "P$41") (pinfunction "CH36_P$41") (pintype "input"))
    )
    (net (code "105") (name "Net-(U$11-CH37)") (class "Default")
      (node (ref "5") (pin "P$2") (pinfunction "P$2_P$2") (pintype "bidirectional"))
      (node (ref "U$11") (pin "P$42") (pinfunction "CH37_P$42") (pintype "input"))
    )
    (net (code "106") (name "Net-(U$11-CH38)") (class "Default")
      (node (ref "5") (pin "P$3") (pinfunction "P$3_P$3") (pintype "bidirectional"))
      (node (ref "U$11") (pin "P$43") (pinfunction "CH38_P$43") (pintype "input"))
    )
    (net (code "107") (name "Net-(U$11-CH39)") (class "Default")
      (node (ref "5") (pin "P$4") (pinfunction "P$4_P$4") (pintype "bidirectional"))
      (node (ref "U$11") (pin "P$44") (pinfunction "CH39_P$44") (pintype "input"))
    )
    (net (code "108") (name "Net-(U$11-CH40)") (class "Default")
      (node (ref "6") (pin "P$1") (pinfunction "P$1_P$1") (pintype "bidirectional"))
      (node (ref "U$11") (pin "P$45") (pinfunction "CH40_P$45") (pintype "input"))
    )
    (net (code "109") (name "Net-(U$11-CH41)") (class "Default")
      (node (ref "6") (pin "P$2") (pinfunction "P$2_P$2") (pintype "bidirectional"))
      (node (ref "U$11") (pin "P$46") (pinfunction "CH41_P$46") (pintype "input"))
    )
    (net (code "110") (name "Net-(U$11-CH42)") (class "Default")
      (node (ref "6") (pin "P$3") (pinfunction "P$3_P$3") (pintype "bidirectional"))
      (node (ref "U$11") (pin "P$47") (pinfunction "CH42_P$47") (pintype "input"))
    )
    (net (code "111") (name "Net-(U$11-CH43)") (class "Default")
      (node (ref "6") (pin "P$4") (pinfunction "P$4_P$4") (pintype "bidirectional"))
      (node (ref "U$11") (pin "P$48") (pinfunction "CH43_P$48") (pintype "input"))
    )
    (net (code "112") (name "Net-(U$11-CH44)") (class "Default")
      (node (ref "7") (pin "P$1") (pinfunction "P$1_P$1") (pintype "bidirectional"))
      (node (ref "U$11") (pin "P$49") (pinfunction "CH44_P$49") (pintype "input"))
    )
    (net (code "113") (name "Net-(U$11-CH45)") (class "Default")
      (node (ref "7") (pin "P$2") (pinfunction "P$2_P$2") (pintype "bidirectional"))
      (node (ref "U$11") (pin "P$50") (pinfunction "CH45_P$50") (pintype "input"))
    )
    (net (code "114") (name "Net-(U$11-CH46)") (class "Default")
      (node (ref "7") (pin "P$3") (pinfunction "P$3_P$3") (pintype "bidirectional"))
      (node (ref "U$11") (pin "P$51") (pinfunction "CH46_P$51") (pintype "input"))
    )
    (net (code "115") (name "Net-(U$11-CH47)") (class "Default")
      (node (ref "7") (pin "P$4") (pinfunction "P$4_P$4") (pintype "bidirectional"))
      (node (ref "U$11") (pin "P$52") (pinfunction "CH47_P$52") (pintype "input"))
    )
    (net (code "116") (name "Net-(U$11-CH48)") (class "Default")
      (node (ref "8") (pin "P$1") (pinfunction "P$1_P$1") (pintype "bidirectional"))
      (node (ref "U$11") (pin "P$53") (pinfunction "CH48_P$53") (pintype "input"))
    )
    (net (code "117") (name "Net-(U$11-CH49)") (class "Default")
      (node (ref "8") (pin "P$2") (pinfunction "P$2_P$2") (pintype "bidirectional"))
      (node (ref "U$11") (pin "P$54") (pinfunction "CH49_P$54") (pintype "input"))
    )
    (net (code "118") (name "Net-(U$11-CH50)") (class "Default")
      (node (ref "8") (pin "P$3") (pinfunction "P$3_P$3") (pintype "bidirectional"))
      (node (ref "U$11") (pin "P$55") (pinfunction "CH50_P$55") (pintype "input"))
    )
    (net (code "119") (name "Net-(U$11-CH51)") (class "Default")
      (node (ref "8") (pin "P$4") (pinfunction "P$4_P$4") (pintype "bidirectional"))
      (node (ref "U$11") (pin "P$56") (pinfunction "CH51_P$56") (pintype "input"))
    )
    (net (code "120") (name "Net-(U$11-CH52)") (class "Default")
      (node (ref "9") (pin "P$1") (pinfunction "P$1_P$1") (pintype "bidirectional"))
      (node (ref "U$11") (pin "P$57") (pinfunction "CH52_P$57") (pintype "input"))
    )
    (net (code "121") (name "Net-(U$11-CH53)") (class "Default")
      (node (ref "9") (pin "P$2") (pinfunction "P$2_P$2") (pintype "bidirectional"))
      (node (ref "U$11") (pin "P$58") (pinfunction "CH53_P$58") (pintype "input"))
    )
    (net (code "122") (name "Net-(U$11-CH54)") (class "Default")
      (node (ref "9") (pin "P$3") (pinfunction "P$3_P$3") (pintype "bidirectional"))
      (node (ref "U$11") (pin "P$59") (pinfunction "CH54_P$59") (pintype "input"))
    )
    (net (code "123") (name "Net-(U$11-CH55)") (class "Default")
      (node (ref "9") (pin "P$4") (pinfunction "P$4_P$4") (pintype "bidirectional"))
      (node (ref "U$11") (pin "P$60") (pinfunction "CH55_P$60") (pintype "input"))
    )
    (net (code "124") (name "Net-(U$11-CH56)") (class "Default")
      (node (ref "10") (pin "P$1") (pinfunction "P$1_P$1") (pintype "bidirectional"))
      (node (ref "U$11") (pin "P$61") (pinfunction "CH56_P$61") (pintype "input"))
    )
    (net (code "125") (name "Net-(U$11-CH57)") (class "Default")
      (node (ref "10") (pin "P$2") (pinfunction "P$2_P$2") (pintype "bidirectional"))
      (node (ref "U$11") (pin "P$62") (pinfunction "CH57_P$62") (pintype "input"))
    )
    (net (code "126") (name "Net-(U$11-CH58)") (class "Default")
      (node (ref "10") (pin "P$3") (pinfunction "P$3_P$3") (pintype "bidirectional"))
      (node (ref "U$11") (pin "P$63") (pinfunction "CH58_P$63") (pintype "input"))
    )
    (net (code "127") (name "Net-(U$11-CH59)") (class "Default")
      (node (ref "10") (pin "P$4") (pinfunction "P$4_P$4") (pintype "bidirectional"))
      (node (ref "U$11") (pin "P$64") (pinfunction "CH59_P$64") (pintype "input"))
    )
    (net (code "128") (name "Net-(U$11-CH60)") (class "Default")
      (node (ref "11") (pin "P$1") (pinfunction "P$1_P$1") (pintype "bidirectional"))
      (node (ref "U$11") (pin "P$65") (pinfunction "CH60_P$65") (pintype "input"))
    )
    (net (code "129") (name "Net-(U$11-CH61)") (class "Default")
      (node (ref "11") (pin "P$2") (pinfunction "P$2_P$2") (pintype "bidirectional"))
      (node (ref "U$11") (pin "P$66") (pinfunction "CH61_P$66") (pintype "input"))
    )
    (net (code "130") (name "Net-(U$11-CH62)") (class "Default")
      (node (ref "11") (pin "P$3") (pinfunction "P$3_P$3") (pintype "bidirectional"))
      (node (ref "U$11") (pin "P$67") (pinfunction "CH62_P$67") (pintype "input"))
    )
    (net (code "131") (name "Net-(U$11-CH63)") (class "Default")
      (node (ref "11") (pin "P$4") (pinfunction "P$4_P$4") (pintype "bidirectional"))
      (node (ref "U$11") (pin "P$68") (pinfunction "CH63_P$68") (pintype "input"))
    )
    (net (code "132") (name "Net-(U$11-REF1)") (class "Default")
      (node (ref "U$11") (pin "P$69") (pinfunction "REF1_P$69") (pintype "input"))
      (node (ref "U$9") (pin "P$1") (pinfunction "P$1_P$1") (pintype "bidirectional"))
    )
    (net (code "133") (name "Net-(U$11-REF64)") (class "Default")
      (node (ref "U$11") (pin "P$34") (pinfunction "REF64_P$34") (pintype "input"))
      (node (ref "U$8") (pin "P$1") (pinfunction "P$1_P$1") (pintype "bidirectional"))
    )
  )
)
